# Audio_VU_LED.net
KiCad netlist of a schematic drawn in Altium Designer
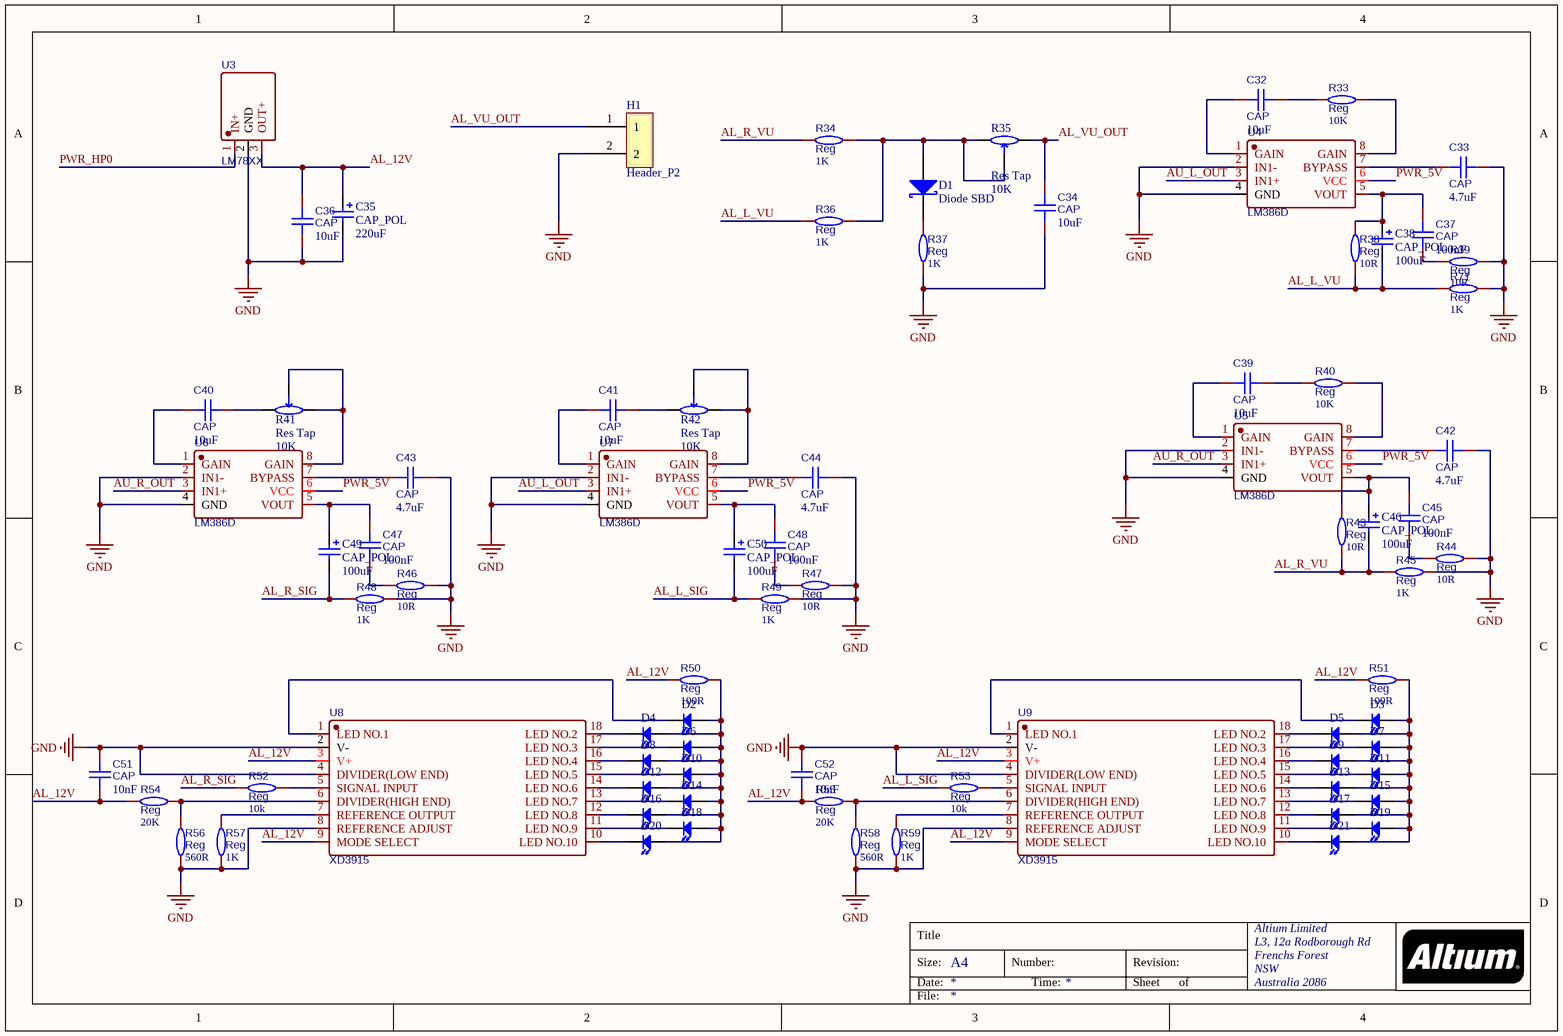
[diagram p0: Audio_VU_LED.SchDoc]

(export (version "E")
  (design (tool "Eeschema 10.0.6"))
  (components
    (comp (ref "C32")
      (value "CAP")
      (footprint "C0603")
      (description "Cap")
      (fields
        (field (name "BOM_SUPPLIER PART") "C302008")
        (field (name "BOM_MANUFACTURER PART") "0603B103K101CT")
        (field (name "ALTIUM_VALUE") "10uF")
        (field (name "CONTRIBUTOR") "LCSC")
      )
      (libsource (lib "Levent_lib") (part "CAP"))
    )
    (comp (ref "C33")
      (value "CAP")
      (footprint "C0603")
      (description "Cap")
      (fields
        (field (name "BOM_SUPPLIER PART") "C302008")
        (field (name "BOM_MANUFACTURER PART") "0603B103K101CT")
        (field (name "ALTIUM_VALUE") "4.7uF")
        (field (name "CONTRIBUTOR") "LCSC")
      )
      (libsource (lib "Levent_lib") (part "CAP"))
    )
    (comp (ref "C34")
      (value "CAP")
      (footprint "C0603")
      (description "Cap")
      (fields
        (field (name "BOM_SUPPLIER PART") "C302008")
        (field (name "BOM_MANUFACTURER PART") "0603B103K101CT")
        (field (name "ALTIUM_VALUE") "10uF")
        (field (name "CONTRIBUTOR") "LCSC")
      )
      (libsource (lib "Levent_lib") (part "CAP"))
    )
    (comp (ref "C35")
      (value "CAP_POL")
      (footprint "CAP_SMD_6.3mm")
      (description "极性电容")
      (fields (field (name "ALTIUM_VALUE") "220uF"))
      (libsource (lib "Levent_lib") (part "CAP_POL"))
    )
    (comp (ref "C36")
      (value "CAP")
      (footprint "C0603")
      (description "Cap")
      (fields
        (field (name "BOM_SUPPLIER PART") "C302008")
        (field (name "BOM_MANUFACTURER PART") "0603B103K101CT")
        (field (name "ALTIUM_VALUE") "10uF")
        (field (name "CONTRIBUTOR") "LCSC")
      )
      (libsource (lib "Levent_lib") (part "CAP"))
    )
    (comp (ref "C37")
      (value "CAP")
      (footprint "C0603")
      (description "Cap")
      (fields
        (field (name "BOM_SUPPLIER PART") "C302008")
        (field (name "BOM_MANUFACTURER PART") "0603B103K101CT")
        (field (name "ALTIUM_VALUE") "100nF")
        (field (name "CONTRIBUTOR") "LCSC")
      )
      (libsource (lib "Levent_lib") (part "CAP"))
    )
    (comp (ref "C38")
      (value "CAP_POL")
      (footprint "CAP_SMD_6.3mm")
      (description "极性电容")
      (fields (field (name "ALTIUM_VALUE") "100uF"))
      (libsource (lib "Levent_lib") (part "CAP_POL"))
    )
    (comp (ref "C39")
      (value "CAP")
      (footprint "C0603")
      (description "Cap")
      (fields
        (field (name "BOM_SUPPLIER PART") "C302008")
        (field (name "BOM_MANUFACTURER PART") "0603B103K101CT")
        (field (name "ALTIUM_VALUE") "10uF")
        (field (name "CONTRIBUTOR") "LCSC")
      )
      (libsource (lib "Levent_lib") (part "CAP"))
    )
    (comp (ref "C40")
      (value "CAP")
      (footprint "C0603")
      (description "Cap")
      (fields
        (field (name "BOM_SUPPLIER PART") "C302008")
        (field (name "BOM_MANUFACTURER PART") "0603B103K101CT")
        (field (name "ALTIUM_VALUE") "10uF")
        (field (name "CONTRIBUTOR") "LCSC")
      )
      (libsource (lib "Levent_lib") (part "CAP"))
    )
    (comp (ref "C41")
      (value "CAP")
      (footprint "C0603")
      (description "Cap")
      (fields
        (field (name "BOM_SUPPLIER PART") "C302008")
        (field (name "BOM_MANUFACTURER PART") "0603B103K101CT")
        (field (name "ALTIUM_VALUE") "10uF")
        (field (name "CONTRIBUTOR") "LCSC")
      )
      (libsource (lib "Levent_lib") (part "CAP"))
    )
    (comp (ref "C42")
      (value "CAP")
      (footprint "C0603")
      (description "Cap")
      (fields
        (field (name "BOM_SUPPLIER PART") "C302008")
        (field (name "BOM_MANUFACTURER PART") "0603B103K101CT")
        (field (name "ALTIUM_VALUE") "4.7uF")
        (field (name "CONTRIBUTOR") "LCSC")
      )
      (libsource (lib "Levent_lib") (part "CAP"))
    )
    (comp (ref "C43")
      (value "CAP")
      (footprint "C0603")
      (description "Cap")
      (fields
        (field (name "BOM_SUPPLIER PART") "C302008")
        (field (name "BOM_MANUFACTURER PART") "0603B103K101CT")
        (field (name "ALTIUM_VALUE") "4.7uF")
        (field (name "CONTRIBUTOR") "LCSC")
      )
      (libsource (lib "Levent_lib") (part "CAP"))
    )
    (comp (ref "C44")
      (value "CAP")
      (footprint "C0603")
      (description "Cap")
      (fields
        (field (name "BOM_SUPPLIER PART") "C302008")
        (field (name "BOM_MANUFACTURER PART") "0603B103K101CT")
        (field (name "ALTIUM_VALUE") "4.7uF")
        (field (name "CONTRIBUTOR") "LCSC")
      )
      (libsource (lib "Levent_lib") (part "CAP"))
    )
    (comp (ref "C45")
      (value "CAP")
      (footprint "C0603")
      (description "Cap")
      (fields
        (field (name "BOM_SUPPLIER PART") "C302008")
        (field (name "BOM_MANUFACTURER PART") "0603B103K101CT")
        (field (name "ALTIUM_VALUE") "100nF")
        (field (name "CONTRIBUTOR") "LCSC")
      )
      (libsource (lib "Levent_lib") (part "CAP"))
    )
    (comp (ref "C46")
      (value "CAP_POL")
      (footprint "CAP_SMD_6.3mm")
      (description "极性电容")
      (fields (field (name "ALTIUM_VALUE") "100uF"))
      (libsource (lib "Levent_lib") (part "CAP_POL"))
    )
    (comp (ref "C47")
      (value "CAP")
      (footprint "C0603")
      (description "Cap")
      (fields
        (field (name "BOM_SUPPLIER PART") "C302008")
        (field (name "BOM_MANUFACTURER PART") "0603B103K101CT")
        (field (name "ALTIUM_VALUE") "100nF")
        (field (name "CONTRIBUTOR") "LCSC")
      )
      (libsource (lib "Levent_lib") (part "CAP"))
    )
    (comp (ref "C48")
      (value "CAP")
      (footprint "C0603")
      (description "Cap")
      (fields
        (field (name "BOM_SUPPLIER PART") "C302008")
        (field (name "BOM_MANUFACTURER PART") "0603B103K101CT")
        (field (name "ALTIUM_VALUE") "100nF")
        (field (name "CONTRIBUTOR") "LCSC")
      )
      (libsource (lib "Levent_lib") (part "CAP"))
    )
    (comp (ref "C49")
      (value "CAP_POL")
      (footprint "CAP_SMD_6.3mm")
      (description "极性电容")
      (fields (field (name "ALTIUM_VALUE") "100uF"))
      (libsource (lib "Levent_lib") (part "CAP_POL"))
    )
    (comp (ref "C50")
      (value "CAP_POL")
      (footprint "CAP_SMD_6.3mm")
      (description "极性电容")
      (fields (field (name "ALTIUM_VALUE") "100uF"))
      (libsource (lib "Levent_lib") (part "CAP_POL"))
    )
    (comp (ref "C51")
      (value "CAP")
      (footprint "C0603")
      (description "Cap")
      (fields
        (field (name "BOM_SUPPLIER PART") "C302008")
        (field (name "BOM_MANUFACTURER PART") "0603B103K101CT")
        (field (name "ALTIUM_VALUE") "10nF")
        (field (name "CONTRIBUTOR") "LCSC")
      )
      (libsource (lib "Levent_lib") (part "CAP"))
    )
    (comp (ref "C52")
      (value "CAP")
      (footprint "C0603")
      (description "Cap")
      (fields
        (field (name "BOM_SUPPLIER PART") "C302008")
        (field (name "BOM_MANUFACTURER PART") "0603B103K101CT")
        (field (name "ALTIUM_VALUE") "10nF")
        (field (name "CONTRIBUTOR") "LCSC")
      )
      (libsource (lib "Levent_lib") (part "CAP"))
    )
    (comp (ref "D1")
      (value "Diode SBD")
      (footprint "SMA_L4.3")
      (description "Schottky Rectifier")
      (fields (field (name "PUBLISHER") "Altium Limited"))
      (libsource (lib "Levent_lib") (part "Diode SBD"))
    )
    (comp (ref "D2")
      (value "LED")
      (footprint "LED0603_Side")
      (fields (field (name "PUBLISHER") "Altium Limited"))
      (libsource (lib "Levent_lib") (part "LED0"))
    )
    (comp (ref "D3")
      (value "LED")
      (footprint "LED0603_Side")
      (fields (field (name "PUBLISHER") "Altium Limited"))
      (libsource (lib "Levent_lib") (part "LED0"))
    )
    (comp (ref "D4")
      (value "LED")
      (footprint "LED0603_Side")
      (fields (field (name "PUBLISHER") "Altium Limited"))
      (libsource (lib "Levent_lib") (part "LED0"))
    )
    (comp (ref "D5")
      (value "LED")
      (footprint "LED0603_Side")
      (fields (field (name "PUBLISHER") "Altium Limited"))
      (libsource (lib "Levent_lib") (part "LED0"))
    )
    (comp (ref "D6")
      (value "LED")
      (footprint "LED0603_Side")
      (fields (field (name "PUBLISHER") "Altium Limited"))
      (libsource (lib "Levent_lib") (part "LED0"))
    )
    (comp (ref "D7")
      (value "LED")
      (footprint "LED0603_Side")
      (fields (field (name "PUBLISHER") "Altium Limited"))
      (libsource (lib "Levent_lib") (part "LED0"))
    )
    (comp (ref "D8")
      (value "LED")
      (footprint "LED0603_Side")
      (fields (field (name "PUBLISHER") "Altium Limited"))
      (libsource (lib "Levent_lib") (part "LED0"))
    )
    (comp (ref "D9")
      (value "LED")
      (footprint "LED0603_Side")
      (fields (field (name "PUBLISHER") "Altium Limited"))
      (libsource (lib "Levent_lib") (part "LED0"))
    )
    (comp (ref "D10")
      (value "LED")
      (footprint "LED0603_Side")
      (fields (field (name "PUBLISHER") "Altium Limited"))
      (libsource (lib "Levent_lib") (part "LED0"))
    )
    (comp (ref "D11")
      (value "LED")
      (footprint "LED0603_Side")
      (fields (field (name "PUBLISHER") "Altium Limited"))
      (libsource (lib "Levent_lib") (part "LED0"))
    )
    (comp (ref "D12")
      (value "LED")
      (footprint "LED0603_Side")
      (fields (field (name "PUBLISHER") "Altium Limited"))
      (libsource (lib "Levent_lib") (part "LED0"))
    )
    (comp (ref "D13")
      (value "LED")
      (footprint "LED0603_Side")
      (fields (field (name "PUBLISHER") "Altium Limited"))
      (libsource (lib "Levent_lib") (part "LED0"))
    )
    (comp (ref "D14")
      (value "LED")
      (footprint "LED0603_Side")
      (fields (field (name "PUBLISHER") "Altium Limited"))
      (libsource (lib "Levent_lib") (part "LED0"))
    )
    (comp (ref "D15")
      (value "LED")
      (footprint "LED0603_Side")
      (fields (field (name "PUBLISHER") "Altium Limited"))
      (libsource (lib "Levent_lib") (part "LED0"))
    )
    (comp (ref "D16")
      (value "LED")
      (footprint "LED0603_Side")
      (fields (field (name "PUBLISHER") "Altium Limited"))
      (libsource (lib "Levent_lib") (part "LED0"))
    )
    (comp (ref "D17")
      (value "LED")
      (footprint "LED0603_Side")
      (fields (field (name "PUBLISHER") "Altium Limited"))
      (libsource (lib "Levent_lib") (part "LED0"))
    )
    (comp (ref "D18")
      (value "LED")
      (footprint "LED0603_Side")
      (fields (field (name "PUBLISHER") "Altium Limited"))
      (libsource (lib "Levent_lib") (part "LED0"))
    )
    (comp (ref "D19")
      (value "LED")
      (footprint "LED0603_Side")
      (fields (field (name "PUBLISHER") "Altium Limited"))
      (libsource (lib "Levent_lib") (part "LED0"))
    )
    (comp (ref "D20")
      (value "LED")
      (footprint "LED0603_Side")
      (fields (field (name "PUBLISHER") "Altium Limited"))
      (libsource (lib "Levent_lib") (part "LED0"))
    )
    (comp (ref "D21")
      (value "LED")
      (footprint "LED0603_Side")
      (fields (field (name "PUBLISHER") "Altium Limited"))
      (libsource (lib "Levent_lib") (part "LED0"))
    )
    (comp (ref "H1")
      (value "Header_P2")
      (footprint "H_2.54_P2")
      (description "2Pin排针")
      (libsource (lib "Levent_lib") (part "Header_P2"))
    )
    (comp (ref "R33")
      (value "Reg")
      (footprint "R0603")
      (description "电阻")
      (fields
        (field (name "BOM_SUPPLIER PART") "C465721")
        (field (name "BOM_MANUFACTURER PART") "AR03BTCX1002A")
        (field (name "ALTIUM_VALUE") "10K")
        (field (name "CONTRIBUTOR") "LCSC")
      )
      (libsource (lib "Levent_lib") (part "Res"))
    )
    (comp (ref "R34")
      (value "Reg")
      (footprint "R0603")
      (description "电阻")
      (fields
        (field (name "BOM_SUPPLIER PART") "C465721")
        (field (name "BOM_MANUFACTURER PART") "AR03BTCX1002A")
        (field (name "ALTIUM_VALUE") "1K")
        (field (name "CONTRIBUTOR") "LCSC")
      )
      (libsource (lib "Levent_lib") (part "Res"))
    )
    (comp (ref "R35")
      (value "Res Tap")
      (footprint "RES_TAP_HOR")
      (description "可调电阻")
      (fields (field (name "ALTIUM_VALUE") "10K") (field (name "PUBLISHER") "Altium Limited"))
      (libsource (lib "Levent_lib") (part "Res Tap"))
    )
    (comp (ref "R36")
      (value "Reg")
      (footprint "R0603")
      (description "电阻")
      (fields
        (field (name "BOM_SUPPLIER PART") "C465721")
        (field (name "BOM_MANUFACTURER PART") "AR03BTCX1002A")
        (field (name "ALTIUM_VALUE") "1K")
        (field (name "CONTRIBUTOR") "LCSC")
      )
      (libsource (lib "Levent_lib") (part "Res"))
    )
    (comp (ref "R37")
      (value "Reg")
      (footprint "R0603")
      (description "电阻")
      (fields
        (field (name "BOM_SUPPLIER PART") "C465721")
        (field (name "BOM_MANUFACTURER PART") "AR03BTCX1002A")
        (field (name "ALTIUM_VALUE") "1K")
        (field (name "CONTRIBUTOR") "LCSC")
      )
      (libsource (lib "Levent_lib") (part "Res"))
    )
    (comp (ref "R38")
      (value "Reg")
      (footprint "R0603")
      (description "电阻")
      (fields
        (field (name "BOM_SUPPLIER PART") "C465721")
        (field (name "BOM_MANUFACTURER PART") "AR03BTCX1002A")
        (field (name "ALTIUM_VALUE") "10R")
        (field (name "CONTRIBUTOR") "LCSC")
      )
      (libsource (lib "Levent_lib") (part "Res"))
    )
    (comp (ref "R39")
      (value "Reg")
      (footprint "R0603")
      (description "电阻")
      (fields
        (field (name "BOM_SUPPLIER PART") "C465721")
        (field (name "BOM_MANUFACTURER PART") "AR03BTCX1002A")
        (field (name "ALTIUM_VALUE") "10R")
        (field (name "CONTRIBUTOR") "LCSC")
      )
      (libsource (lib "Levent_lib") (part "Res"))
    )
    (comp (ref "R40")
      (value "Reg")
      (footprint "R0603")
      (description "电阻")
      (fields
        (field (name "BOM_SUPPLIER PART") "C465721")
        (field (name "BOM_MANUFACTURER PART") "AR03BTCX1002A")
        (field (name "ALTIUM_VALUE") "10K")
        (field (name "CONTRIBUTOR") "LCSC")
      )
      (libsource (lib "Levent_lib") (part "Res"))
    )
    (comp (ref "R41")
      (value "Res Tap")
      (footprint "RES_TAP_HOR")
      (description "可调电阻")
      (fields (field (name "ALTIUM_VALUE") "10K") (field (name "PUBLISHER") "Altium Limited"))
      (libsource (lib "Levent_lib") (part "Res Tap"))
    )
    (comp (ref "R42")
      (value "Res Tap")
      (footprint "RES_TAP_HOR")
      (description "可调电阻")
      (fields (field (name "ALTIUM_VALUE") "10K") (field (name "PUBLISHER") "Altium Limited"))
      (libsource (lib "Levent_lib") (part "Res Tap"))
    )
    (comp (ref "R43")
      (value "Reg")
      (footprint "R0603")
      (description "电阻")
      (fields
        (field (name "BOM_SUPPLIER PART") "C465721")
        (field (name "BOM_MANUFACTURER PART") "AR03BTCX1002A")
        (field (name "ALTIUM_VALUE") "10R")
        (field (name "CONTRIBUTOR") "LCSC")
      )
      (libsource (lib "Levent_lib") (part "Res"))
    )
    (comp (ref "R44")
      (value "Reg")
      (footprint "R0603")
      (description "电阻")
      (fields
        (field (name "BOM_SUPPLIER PART") "C465721")
        (field (name "BOM_MANUFACTURER PART") "AR03BTCX1002A")
        (field (name "ALTIUM_VALUE") "10R")
        (field (name "CONTRIBUTOR") "LCSC")
      )
      (libsource (lib "Levent_lib") (part "Res"))
    )
    (comp (ref "R45")
      (value "Reg")
      (footprint "R0603")
      (description "电阻")
      (fields
        (field (name "BOM_SUPPLIER PART") "C465721")
        (field (name "BOM_MANUFACTURER PART") "AR03BTCX1002A")
        (field (name "ALTIUM_VALUE") "1K")
        (field (name "CONTRIBUTOR") "LCSC")
      )
      (libsource (lib "Levent_lib") (part "Res"))
    )
    (comp (ref "R46")
      (value "Reg")
      (footprint "R0603")
      (description "电阻")
      (fields
        (field (name "BOM_SUPPLIER PART") "C465721")
        (field (name "BOM_MANUFACTURER PART") "AR03BTCX1002A")
        (field (name "ALTIUM_VALUE") "10R")
        (field (name "CONTRIBUTOR") "LCSC")
      )
      (libsource (lib "Levent_lib") (part "Res"))
    )
    (comp (ref "R47")
      (value "Reg")
      (footprint "R0603")
      (description "电阻")
      (fields
        (field (name "BOM_SUPPLIER PART") "C465721")
        (field (name "BOM_MANUFACTURER PART") "AR03BTCX1002A")
        (field (name "ALTIUM_VALUE") "10R")
        (field (name "CONTRIBUTOR") "LCSC")
      )
      (libsource (lib "Levent_lib") (part "Res"))
    )
    (comp (ref "R48")
      (value "Reg")
      (footprint "R0603")
      (description "电阻")
      (fields
        (field (name "BOM_SUPPLIER PART") "C465721")
        (field (name "BOM_MANUFACTURER PART") "AR03BTCX1002A")
        (field (name "ALTIUM_VALUE") "1K")
        (field (name "CONTRIBUTOR") "LCSC")
      )
      (libsource (lib "Levent_lib") (part "Res"))
    )
    (comp (ref "R49")
      (value "Reg")
      (footprint "R0603")
      (description "电阻")
      (fields
        (field (name "BOM_SUPPLIER PART") "C465721")
        (field (name "BOM_MANUFACTURER PART") "AR03BTCX1002A")
        (field (name "ALTIUM_VALUE") "1K")
        (field (name "CONTRIBUTOR") "LCSC")
      )
      (libsource (lib "Levent_lib") (part "Res"))
    )
    (comp (ref "R50")
      (value "Reg")
      (footprint "R0603")
      (description "电阻")
      (fields
        (field (name "BOM_SUPPLIER PART") "C465721")
        (field (name "BOM_MANUFACTURER PART") "AR03BTCX1002A")
        (field (name "ALTIUM_VALUE") "100R")
        (field (name "CONTRIBUTOR") "LCSC")
      )
      (libsource (lib "Levent_lib") (part "Res"))
    )
    (comp (ref "R51")
      (value "Reg")
      (footprint "R0603")
      (description "电阻")
      (fields
        (field (name "BOM_SUPPLIER PART") "C465721")
        (field (name "BOM_MANUFACTURER PART") "AR03BTCX1002A")
        (field (name "ALTIUM_VALUE") "100R")
        (field (name "CONTRIBUTOR") "LCSC")
      )
      (libsource (lib "Levent_lib") (part "Res"))
    )
    (comp (ref "R52")
      (value "Reg")
      (footprint "R0603")
      (description "电阻")
      (fields
        (field (name "BOM_SUPPLIER PART") "C465721")
        (field (name "BOM_MANUFACTURER PART") "AR03BTCX1002A")
        (field (name "ALTIUM_VALUE") "10k")
        (field (name "CONTRIBUTOR") "LCSC")
      )
      (libsource (lib "Levent_lib") (part "Res"))
    )
    (comp (ref "R53")
      (value "Reg")
      (footprint "R0603")
      (description "电阻")
      (fields
        (field (name "BOM_SUPPLIER PART") "C465721")
        (field (name "BOM_MANUFACTURER PART") "AR03BTCX1002A")
        (field (name "ALTIUM_VALUE") "10k")
        (field (name "CONTRIBUTOR") "LCSC")
      )
      (libsource (lib "Levent_lib") (part "Res"))
    )
    (comp (ref "R54")
      (value "Reg")
      (footprint "R0603")
      (description "电阻")
      (fields
        (field (name "BOM_SUPPLIER PART") "C465721")
        (field (name "BOM_MANUFACTURER PART") "AR03BTCX1002A")
        (field (name "ALTIUM_VALUE") "20K")
        (field (name "CONTRIBUTOR") "LCSC")
      )
      (libsource (lib "Levent_lib") (part "Res"))
    )
    (comp (ref "R55")
      (value "Reg")
      (footprint "R0603")
      (description "电阻")
      (fields
        (field (name "BOM_SUPPLIER PART") "C465721")
        (field (name "BOM_MANUFACTURER PART") "AR03BTCX1002A")
        (field (name "ALTIUM_VALUE") "20K")
        (field (name "CONTRIBUTOR") "LCSC")
      )
      (libsource (lib "Levent_lib") (part "Res"))
    )
    (comp (ref "R56")
      (value "Reg")
      (footprint "R0603")
      (description "电阻")
      (fields
        (field (name "BOM_SUPPLIER PART") "C465721")
        (field (name "BOM_MANUFACTURER PART") "AR03BTCX1002A")
        (field (name "ALTIUM_VALUE") "560R")
        (field (name "CONTRIBUTOR") "LCSC")
      )
      (libsource (lib "Levent_lib") (part "Res"))
    )
    (comp (ref "R57")
      (value "Reg")
      (footprint "R0603")
      (description "电阻")
      (fields
        (field (name "BOM_SUPPLIER PART") "C465721")
        (field (name "BOM_MANUFACTURER PART") "AR03BTCX1002A")
        (field (name "ALTIUM_VALUE") "1K")
        (field (name "CONTRIBUTOR") "LCSC")
      )
      (libsource (lib "Levent_lib") (part "Res"))
    )
    (comp (ref "R58")
      (value "Reg")
      (footprint "R0603")
      (description "电阻")
      (fields
        (field (name "BOM_SUPPLIER PART") "C465721")
        (field (name "BOM_MANUFACTURER PART") "AR03BTCX1002A")
        (field (name "ALTIUM_VALUE") "560R")
        (field (name "CONTRIBUTOR") "LCSC")
      )
      (libsource (lib "Levent_lib") (part "Res"))
    )
    (comp (ref "R59")
      (value "Reg")
      (footprint "R0603")
      (description "电阻")
      (fields
        (field (name "BOM_SUPPLIER PART") "C465721")
        (field (name "BOM_MANUFACTURER PART") "AR03BTCX1002A")
        (field (name "ALTIUM_VALUE") "1K")
        (field (name "CONTRIBUTOR") "LCSC")
      )
      (libsource (lib "Levent_lib") (part "Res"))
    )
    (comp (ref "R71")
      (value "Reg")
      (footprint "R0603")
      (description "电阻")
      (fields
        (field (name "BOM_SUPPLIER PART") "C465721")
        (field (name "BOM_MANUFACTURER PART") "AR03BTCX1002A")
        (field (name "ALTIUM_VALUE") "1K")
        (field (name "CONTRIBUTOR") "LCSC")
      )
      (libsource (lib "Levent_lib") (part "Res"))
    )
    (comp (ref "U3")
      (value "LM78XX")
      (footprint "TO-220-3_2.54")
      (description "三端稳压(正电压)")
      (fields
        (field (name "BOM_SUPPLIER PART") "C2902509")
        (field (name "BOM_MANUFACTURER PART") "LM7812T")
        (field (name "CONTRIBUTOR") "LCSC")
      )
      (libsource (lib "Levent_lib") (part "LM78XX"))
    )
    (comp (ref "U4")
      (value "LM386D")
      (footprint "SOP-8")
      (description "LM386")
      (fields (field (name "BOM_SUPPLIER PART") "C510560") (field (name "CONTRIBUTOR") "LCSC"))
      (libsource (lib "Levent_lib") (part "LM386D"))
    )
    (comp (ref "U5")
      (value "LM386D")
      (footprint "SOP-8")
      (description "LM386")
      (fields (field (name "BOM_SUPPLIER PART") "C510560") (field (name "CONTRIBUTOR") "LCSC"))
      (libsource (lib "Levent_lib") (part "LM386D"))
    )
    (comp (ref "U6")
      (value "LM386D")
      (footprint "SOP-8")
      (description "LM386")
      (fields (field (name "BOM_SUPPLIER PART") "C510560") (field (name "CONTRIBUTOR") "LCSC"))
      (libsource (lib "Levent_lib") (part "LM386D"))
    )
    (comp (ref "U7")
      (value "LM386D")
      (footprint "SOP-8")
      (description "LM386")
      (fields (field (name "BOM_SUPPLIER PART") "C510560") (field (name "CONTRIBUTOR") "LCSC"))
      (libsource (lib "Levent_lib") (part "LM386D"))
    )
    (comp (ref "U8")
      (value "XD3915")
      (footprint "DIP-18")
      (description "电平指示")
      (fields (field (name "BOM_SUPPLIER PART") "C609778") (field (name "CONTRIBUTOR") "LCSC"))
      (libsource (lib "Levent_lib") (part "LM3915"))
    )
    (comp (ref "U9")
      (value "XD3915")
      (footprint "DIP-18")
      (description "电平指示")
      (fields (field (name "BOM_SUPPLIER PART") "C609778") (field (name "CONTRIBUTOR") "LCSC"))
      (libsource (lib "Levent_lib") (part "LM3915"))
    )
  )
  (nets
    (net (code "1") (name "/AL_12V") (class "Default")
      (node (ref "C35") (pin "1") (pinfunction "1_1") (pintype "passive"))
      (node (ref "C36") (pin "1") (pinfunction "1_1") (pintype "passive"))
      (node (ref "C51") (pin "1") (pinfunction "1_1") (pintype "passive"))
      (node (ref "C52") (pin "1") (pinfunction "1_1") (pintype "passive"))
      (node (ref "R50") (pin "1") (pinfunction "1_1") (pintype "passive"))
      (node (ref "R51") (pin "1") (pinfunction "1_1") (pintype "passive"))
      (node (ref "R54") (pin "2") (pinfunction "2_2") (pintype "passive"))
      (node (ref "R55") (pin "2") (pinfunction "2_2") (pintype "passive"))
      (node (ref "U3") (pin "3") (pinfunction "OUT+_3") (pintype "passive"))
      (node (ref "U8") (pin "3") (pinfunction "V+_3") (pintype "passive"))
      (node (ref "U8") (pin "9") (pinfunction "MODE_SELECT_9") (pintype "passive"))
      (node (ref "U9") (pin "3") (pinfunction "V+_3") (pintype "passive"))
      (node (ref "U9") (pin "9") (pinfunction "MODE_SELECT_9") (pintype "passive"))
    )
    (net (code "2") (name "/AL_L_SIG") (class "Default")
      (node (ref "C50") (pin "2") (pinfunction "2_2") (pintype "passive"))
      (node (ref "R49") (pin "2") (pinfunction "2_2") (pintype "passive"))
      (node (ref "R53") (pin "2") (pinfunction "2_2") (pintype "passive"))
    )
    (net (code "3") (name "/AL_L_VU") (class "Default")
      (node (ref "C38") (pin "2") (pinfunction "2_2") (pintype "passive"))
      (node (ref "R36") (pin "2") (pinfunction "2_2") (pintype "passive"))
      (node (ref "R38") (pin "2") (pinfunction "2_2") (pintype "passive"))
      (node (ref "R71") (pin "2") (pinfunction "2_2") (pintype "passive"))
    )
    (net (code "4") (name "/AL_R_SIG") (class "Default")
      (node (ref "C49") (pin "2") (pinfunction "2_2") (pintype "passive"))
      (node (ref "R48") (pin "2") (pinfunction "2_2") (pintype "passive"))
      (node (ref "R52") (pin "2") (pinfunction "2_2") (pintype "passive"))
    )
    (net (code "5") (name "/AL_R_VU") (class "Default")
      (node (ref "C46") (pin "2") (pinfunction "2_2") (pintype "passive"))
      (node (ref "R34") (pin "2") (pinfunction "2_2") (pintype "passive"))
      (node (ref "R43") (pin "2") (pinfunction "2_2") (pintype "passive"))
      (node (ref "R45") (pin "2") (pinfunction "2_2") (pintype "passive"))
    )
    (net (code "6") (name "/AL_VU_OUT") (class "Default")
      (node (ref "C34") (pin "1") (pinfunction "1_1") (pintype "passive"))
      (node (ref "H1") (pin "1") (pinfunction "1_1") (pintype "passive"))
      (node (ref "R35") (pin "1") (pinfunction "A_1") (pintype "passive"))
    )
    (net (code "7") (name "/AU_L_OUT") (class "Default")
      (node (ref "U4") (pin "3") (pinfunction "IN1+_3") (pintype "passive"))
      (node (ref "U7") (pin "3") (pinfunction "IN1+_3") (pintype "passive"))
    )
    (net (code "8") (name "/AU_R_OUT") (class "Default")
      (node (ref "U5") (pin "3") (pinfunction "IN1+_3") (pintype "passive"))
      (node (ref "U6") (pin "3") (pinfunction "IN1+_3") (pintype "passive"))
    )
    (net (code "9") (name "/PWR_5V") (class "Default")
      (node (ref "U4") (pin "6") (pinfunction "VCC_6") (pintype "passive"))
      (node (ref "U5") (pin "6") (pinfunction "VCC_6") (pintype "passive"))
      (node (ref "U6") (pin "6") (pinfunction "VCC_6") (pintype "passive"))
      (node (ref "U7") (pin "6") (pinfunction "VCC_6") (pintype "passive"))
    )
    (net (code "10") (name "/PWR_HP0") (class "Default")
      (node (ref "U3") (pin "1") (pinfunction "IN+_1") (pintype "passive"))
    )
    (net (code "11") (name "GND") (class "Default")
      (node (ref "C33") (pin "2") (pinfunction "2_2") (pintype "passive"))
      (node (ref "C34") (pin "2") (pinfunction "2_2") (pintype "passive"))
      (node (ref "C35") (pin "2") (pinfunction "2_2") (pintype "passive"))
      (node (ref "C36") (pin "2") (pinfunction "2_2") (pintype "passive"))
      (node (ref "C42") (pin "2") (pinfunction "2_2") (pintype "passive"))
      (node (ref "C43") (pin "2") (pinfunction "2_2") (pintype "passive"))
      (node (ref "C44") (pin "2") (pinfunction "2_2") (pintype "passive"))
      (node (ref "C51") (pin "2") (pinfunction "2_2") (pintype "passive"))
      (node (ref "C52") (pin "2") (pinfunction "2_2") (pintype "passive"))
      (node (ref "H1") (pin "2") (pinfunction "2_2") (pintype "passive"))
      (node (ref "R37") (pin "2") (pinfunction "2_2") (pintype "passive"))
      (node (ref "R39") (pin "1") (pinfunction "1_1") (pintype "passive"))
      (node (ref "R44") (pin "1") (pinfunction "1_1") (pintype "passive"))
      (node (ref "R45") (pin "1") (pinfunction "1_1") (pintype "passive"))
      (node (ref "R46") (pin "1") (pinfunction "1_1") (pintype "passive"))
      (node (ref "R47") (pin "1") (pinfunction "1_1") (pintype "passive"))
      (node (ref "R48") (pin "1") (pinfunction "1_1") (pintype "passive"))
      (node (ref "R49") (pin "1") (pinfunction "1_1") (pintype "passive"))
      (node (ref "R56") (pin "2") (pinfunction "2_2") (pintype "passive"))
      (node (ref "R57") (pin "2") (pinfunction "2_2") (pintype "passive"))
      (node (ref "R58") (pin "2") (pinfunction "2_2") (pintype "passive"))
      (node (ref "R59") (pin "2") (pinfunction "2_2") (pintype "passive"))
      (node (ref "R71") (pin "1") (pinfunction "1_1") (pintype "passive"))
      (node (ref "U3") (pin "2") (pinfunction "GND_2") (pintype "passive"))
      (node (ref "U4") (pin "2") (pinfunction "IN1-_2") (pintype "passive"))
      (node (ref "U4") (pin "4") (pinfunction "GND_4") (pintype "passive"))
      (node (ref "U5") (pin "2") (pinfunction "IN1-_2") (pintype "passive"))
      (node (ref "U5") (pin "4") (pinfunction "GND_4") (pintype "passive"))
      (node (ref "U6") (pin "2") (pinfunction "IN1-_2") (pintype "passive"))
      (node (ref "U6") (pin "4") (pinfunction "GND_4") (pintype "passive"))
      (node (ref "U7") (pin "2") (pinfunction "IN1-_2") (pintype "passive"))
      (node (ref "U7") (pin "4") (pinfunction "GND_4") (pintype "passive"))
      (node (ref "U8") (pin "2") (pinfunction "V-_2") (pintype "passive"))
      (node (ref "U8") (pin "4") (pinfunction "DIVIDER(LOW_END)_4") (pintype "passive"))
      (node (ref "U8") (pin "8") (pinfunction "REFERENCE_ADJUST_8") (pintype "passive"))
      (node (ref "U9") (pin "2") (pinfunction "V-_2") (pintype "passive"))
      (node (ref "U9") (pin "4") (pinfunction "DIVIDER(LOW_END)_4") (pintype "passive"))
      (node (ref "U9") (pin "8") (pinfunction "REFERENCE_ADJUST_8") (pintype "passive"))
    )
    (net (code "12") (name "Net-(C32-Pad1)") (class "Default")
      (node (ref "C32") (pin "1") (pinfunction "1_1") (pintype "passive"))
      (node (ref "U4") (pin "1") (pinfunction "GAIN_1") (pintype "passive"))
    )
    (net (code "13") (name "Net-(C32-Pad2)") (class "Default")
      (node (ref "C32") (pin "2") (pinfunction "2_2") (pintype "passive"))
      (node (ref "R33") (pin "2") (pinfunction "2_2") (pintype "passive"))
    )
    (net (code "14") (name "Net-(C37-Pad1)") (class "Default")
      (node (ref "C37") (pin "1") (pinfunction "1_1") (pintype "passive"))
      (node (ref "R39") (pin "2") (pinfunction "2_2") (pintype "passive"))
    )
    (net (code "15") (name "Net-(C39-Pad1)") (class "Default")
      (node (ref "C39") (pin "1") (pinfunction "1_1") (pintype "passive"))
      (node (ref "U5") (pin "1") (pinfunction "GAIN_1") (pintype "passive"))
    )
    (net (code "16") (name "Net-(C39-Pad2)") (class "Default")
      (node (ref "C39") (pin "2") (pinfunction "2_2") (pintype "passive"))
      (node (ref "R40") (pin "2") (pinfunction "2_2") (pintype "passive"))
    )
    (net (code "17") (name "Net-(C40-Pad1)") (class "Default")
      (node (ref "C40") (pin "1") (pinfunction "1_1") (pintype "passive"))
      (node (ref "U6") (pin "1") (pinfunction "GAIN_1") (pintype "passive"))
    )
    (net (code "18") (name "Net-(C41-Pad1)") (class "Default")
      (node (ref "C41") (pin "1") (pinfunction "1_1") (pintype "passive"))
      (node (ref "U7") (pin "1") (pinfunction "GAIN_1") (pintype "passive"))
    )
    (net (code "19") (name "Net-(C45-Pad1)") (class "Default")
      (node (ref "C45") (pin "1") (pinfunction "1_1") (pintype "passive"))
      (node (ref "R44") (pin "2") (pinfunction "2_2") (pintype "passive"))
    )
    (net (code "20") (name "Net-(C47-Pad1)") (class "Default")
      (node (ref "C47") (pin "1") (pinfunction "1_1") (pintype "passive"))
      (node (ref "R46") (pin "2") (pinfunction "2_2") (pintype "passive"))
    )
    (net (code "21") (name "Net-(C48-Pad1)") (class "Default")
      (node (ref "C48") (pin "1") (pinfunction "1_1") (pintype "passive"))
      (node (ref "R47") (pin "2") (pinfunction "2_2") (pintype "passive"))
    )
    (net (code "22") (name "Net-(D1-A)") (class "Default")
      (node (ref "D1") (pin "2") (pinfunction "A_2") (pintype "passive"))
      (node (ref "R34") (pin "1") (pinfunction "1_1") (pintype "passive"))
      (node (ref "R35") (pin "2") (pinfunction "B_2") (pintype "passive"))
      (node (ref "R35") (pin "3") (pinfunction "TAP_3") (pintype "passive"))
      (node (ref "R36") (pin "1") (pinfunction "1_1") (pintype "passive"))
    )
    (net (code "23") (name "Net-(D1-K)") (class "Default")
      (node (ref "D1") (pin "1") (pinfunction "K_1") (pintype "passive"))
      (node (ref "R37") (pin "1") (pinfunction "1_1") (pintype "passive"))
    )
    (net (code "24") (name "Net-(D2-K)") (class "Default")
      (node (ref "D2") (pin "1") (pinfunction "K_1") (pintype "passive"))
      (node (ref "U8") (pin "1") (pinfunction "LED_NO.1_1") (pintype "passive"))
    )
    (net (code "25") (name "Net-(D3-K)") (class "Default")
      (node (ref "D3") (pin "1") (pinfunction "K_1") (pintype "passive"))
      (node (ref "U9") (pin "1") (pinfunction "LED_NO.1_1") (pintype "passive"))
    )
    (net (code "26") (name "Net-(D4-K)") (class "Default")
      (node (ref "D4") (pin "1") (pinfunction "K_1") (pintype "passive"))
      (node (ref "U8") (pin "18") (pinfunction "LED_NO.2_18") (pintype "passive"))
    )
    (net (code "27") (name "Net-(D5-K)") (class "Default")
      (node (ref "D5") (pin "1") (pinfunction "K_1") (pintype "passive"))
      (node (ref "U9") (pin "18") (pinfunction "LED_NO.2_18") (pintype "passive"))
    )
    (net (code "28") (name "Net-(D6-K)") (class "Default")
      (node (ref "D6") (pin "1") (pinfunction "K_1") (pintype "passive"))
      (node (ref "U8") (pin "17") (pinfunction "LED_NO.3_17") (pintype "passive"))
    )
    (net (code "29") (name "Net-(D7-K)") (class "Default")
      (node (ref "D7") (pin "1") (pinfunction "K_1") (pintype "passive"))
      (node (ref "U9") (pin "17") (pinfunction "LED_NO.3_17") (pintype "passive"))
    )
    (net (code "30") (name "Net-(D8-K)") (class "Default")
      (node (ref "D8") (pin "1") (pinfunction "K_1") (pintype "passive"))
      (node (ref "U8") (pin "16") (pinfunction "LED_NO.4_16") (pintype "passive"))
    )
    (net (code "31") (name "Net-(D9-K)") (class "Default")
      (node (ref "D9") (pin "1") (pinfunction "K_1") (pintype "passive"))
      (node (ref "U9") (pin "16") (pinfunction "LED_NO.4_16") (pintype "passive"))
    )
    (net (code "32") (name "Net-(D10-A)") (class "Default")
      (node (ref "D10") (pin "2") (pinfunction "A_2") (pintype "passive"))
      (node (ref "D12") (pin "2") (pinfunction "A_2") (pintype "passive"))
      (node (ref "D14") (pin "2") (pinfunction "A_2") (pintype "passive"))
      (node (ref "D16") (pin "2") (pinfunction "A_2") (pintype "passive"))
      (node (ref "D18") (pin "2") (pinfunction "A_2") (pintype "passive"))
      (node (ref "D2") (pin "2") (pinfunction "A_2") (pintype "passive"))
      (node (ref "D20") (pin "2") (pinfunction "A_2") (pintype "passive"))
      (node (ref "D4") (pin "2") (pinfunction "A_2") (pintype "passive"))
      (node (ref "D6") (pin "2") (pinfunction "A_2") (pintype "passive"))
      (node (ref "D8") (pin "2") (pinfunction "A_2") (pintype "passive"))
      (node (ref "R50") (pin "2") (pinfunction "2_2") (pintype "passive"))
    )
    (net (code "33") (name "Net-(D10-K)") (class "Default")
      (node (ref "D10") (pin "1") (pinfunction "K_1") (pintype "passive"))
      (node (ref "U8") (pin "15") (pinfunction "LED_NO.5_15") (pintype "passive"))
    )
    (net (code "34") (name "Net-(D11-A)") (class "Default")
      (node (ref "D11") (pin "2") (pinfunction "A_2") (pintype "passive"))
      (node (ref "D13") (pin "2") (pinfunction "A_2") (pintype "passive"))
      (node (ref "D15") (pin "2") (pinfunction "A_2") (pintype "passive"))
      (node (ref "D17") (pin "2") (pinfunction "A_2") (pintype "passive"))
      (node (ref "D19") (pin "2") (pinfunction "A_2") (pintype "passive"))
      (node (ref "D21") (pin "2") (pinfunction "A_2") (pintype "passive"))
      (node (ref "D3") (pin "2") (pinfunction "A_2") (pintype "passive"))
      (node (ref "D5") (pin "2") (pinfunction "A_2") (pintype "passive"))
      (node (ref "D7") (pin "2") (pinfunction "A_2") (pintype "passive"))
      (node (ref "D9") (pin "2") (pinfunction "A_2") (pintype "passive"))
      (node (ref "R51") (pin "2") (pinfunction "2_2") (pintype "passive"))
    )
    (net (code "35") (name "Net-(D11-K)") (class "Default")
      (node (ref "D11") (pin "1") (pinfunction "K_1") (pintype "passive"))
      (node (ref "U9") (pin "15") (pinfunction "LED_NO.5_15") (pintype "passive"))
    )
    (net (code "36") (name "Net-(D12-K)") (class "Default")
      (node (ref "D12") (pin "1") (pinfunction "K_1") (pintype "passive"))
      (node (ref "U8") (pin "14") (pinfunction "LED_NO.6_14") (pintype "passive"))
    )
    (net (code "37") (name "Net-(D13-K)") (class "Default")
      (node (ref "D13") (pin "1") (pinfunction "K_1") (pintype "passive"))
      (node (ref "U9") (pin "14") (pinfunction "LED_NO.6_14") (pintype "passive"))
    )
    (net (code "38") (name "Net-(D14-K)") (class "Default")
      (node (ref "D14") (pin "1") (pinfunction "K_1") (pintype "passive"))
      (node (ref "U8") (pin "13") (pinfunction "LED_NO.7_13") (pintype "passive"))
    )
    (net (code "39") (name "Net-(D15-K)") (class "Default")
      (node (ref "D15") (pin "1") (pinfunction "K_1") (pintype "passive"))
      (node (ref "U9") (pin "13") (pinfunction "LED_NO.7_13") (pintype "passive"))
    )
    (net (code "40") (name "Net-(D16-K)") (class "Default")
      (node (ref "D16") (pin "1") (pinfunction "K_1") (pintype "passive"))
      (node (ref "U8") (pin "12") (pinfunction "LED_NO.8_12") (pintype "passive"))
    )
    (net (code "41") (name "Net-(D17-K)") (class "Default")
      (node (ref "D17") (pin "1") (pinfunction "K_1") (pintype "passive"))
      (node (ref "U9") (pin "12") (pinfunction "LED_NO.8_12") (pintype "passive"))
    )
    (net (code "42") (name "Net-(D18-K)") (class "Default")
      (node (ref "D18") (pin "1") (pinfunction "K_1") (pintype "passive"))
      (node (ref "U8") (pin "11") (pinfunction "LED_NO.9_11") (pintype "passive"))
    )
    (net (code "43") (name "Net-(D19-K)") (class "Default")
      (node (ref "D19") (pin "1") (pinfunction "K_1") (pintype "passive"))
      (node (ref "U9") (pin "11") (pinfunction "LED_NO.9_11") (pintype "passive"))
    )
    (net (code "44") (name "Net-(D20-K)") (class "Default")
      (node (ref "D20") (pin "1") (pinfunction "K_1") (pintype "passive"))
      (node (ref "U8") (pin "10") (pinfunction "LED_NO.10_10") (pintype "passive"))
    )
    (net (code "45") (name "Net-(D21-K)") (class "Default")
      (node (ref "D21") (pin "1") (pinfunction "K_1") (pintype "passive"))
      (node (ref "U9") (pin "10") (pinfunction "LED_NO.10_10") (pintype "passive"))
    )
    (net (code "46") (name "Net-(R33-Pad1)") (class "Default")
      (node (ref "R33") (pin "1") (pinfunction "1_1") (pintype "passive"))
      (node (ref "U4") (pin "8") (pinfunction "GAIN_8") (pintype "passive"))
    )
    (net (code "47") (name "Net-(R40-Pad1)") (class "Default")
      (node (ref "R40") (pin "1") (pinfunction "1_1") (pintype "passive"))
      (node (ref "U5") (pin "8") (pinfunction "GAIN_8") (pintype "passive"))
    )
    (net (code "48") (name "Net-(R41-A)") (class "Default")
      (node (ref "C40") (pin "2") (pinfunction "2_2") (pintype "passive"))
      (node (ref "R41") (pin "1") (pinfunction "A_1") (pintype "passive"))
    )
    (net (code "49") (name "Net-(R41-B)") (class "Default")
      (node (ref "R41") (pin "2") (pinfunction "B_2") (pintype "passive"))
      (node (ref "R41") (pin "3") (pinfunction "TAP_3") (pintype "passive"))
      (node (ref "U6") (pin "8") (pinfunction "GAIN_8") (pintype "passive"))
    )
    (net (code "50") (name "Net-(R42-A)") (class "Default")
      (node (ref "C41") (pin "2") (pinfunction "2_2") (pintype "passive"))
      (node (ref "R42") (pin "1") (pinfunction "A_1") (pintype "passive"))
    )
    (net (code "51") (name "Net-(R42-B)") (class "Default")
      (node (ref "R42") (pin "2") (pinfunction "B_2") (pintype "passive"))
      (node (ref "R42") (pin "3") (pinfunction "TAP_3") (pintype "passive"))
      (node (ref "U7") (pin "8") (pinfunction "GAIN_8") (pintype "passive"))
    )
    (net (code "52") (name "Net-(U4-BYPASS)") (class "Default")
      (node (ref "C33") (pin "1") (pinfunction "1_1") (pintype "passive"))
      (node (ref "U4") (pin "7") (pinfunction "BYPASS_7") (pintype "passive"))
    )
    (net (code "53") (name "Net-(U4-VOUT)") (class "Default")
      (node (ref "C37") (pin "2") (pinfunction "2_2") (pintype "passive"))
      (node (ref "C38") (pin "1") (pinfunction "1_1") (pintype "passive"))
      (node (ref "R38") (pin "1") (pinfunction "1_1") (pintype "passive"))
      (node (ref "U4") (pin "5") (pinfunction "VOUT_5") (pintype "passive"))
    )
    (net (code "54") (name "Net-(U5-BYPASS)") (class "Default")
      (node (ref "C42") (pin "1") (pinfunction "1_1") (pintype "passive"))
      (node (ref "U5") (pin "7") (pinfunction "BYPASS_7") (pintype "passive"))
    )
    (net (code "55") (name "Net-(U5-VOUT)") (class "Default")
      (node (ref "C45") (pin "2") (pinfunction "2_2") (pintype "passive"))
      (node (ref "C46") (pin "1") (pinfunction "1_1") (pintype "passive"))
      (node (ref "R43") (pin "1") (pinfunction "1_1") (pintype "passive"))
      (node (ref "U5") (pin "5") (pinfunction "VOUT_5") (pintype "passive"))
    )
    (net (code "56") (name "Net-(U6-BYPASS)") (class "Default")
      (node (ref "C43") (pin "1") (pinfunction "1_1") (pintype "passive"))
      (node (ref "U6") (pin "7") (pinfunction "BYPASS_7") (pintype "passive"))
    )
    (net (code "57") (name "Net-(U6-VOUT)") (class "Default")
      (node (ref "C47") (pin "2") (pinfunction "2_2") (pintype "passive"))
      (node (ref "C49") (pin "1") (pinfunction "1_1") (pintype "passive"))
      (node (ref "U6") (pin "5") (pinfunction "VOUT_5") (pintype "passive"))
    )
    (net (code "58") (name "Net-(U7-BYPASS)") (class "Default")
      (node (ref "C44") (pin "1") (pinfunction "1_1") (pintype "passive"))
      (node (ref "U7") (pin "7") (pinfunction "BYPASS_7") (pintype "passive"))
    )
    (net (code "59") (name "Net-(U7-VOUT)") (class "Default")
      (node (ref "C48") (pin "2") (pinfunction "2_2") (pintype "passive"))
      (node (ref "C50") (pin "1") (pinfunction "1_1") (pintype "passive"))
      (node (ref "U7") (pin "5") (pinfunction "VOUT_5") (pintype "passive"))
    )
    (net (code "60") (name "Net-(U8-DIVIDER(HIGH_END))") (class "Default")
      (node (ref "R54") (pin "1") (pinfunction "1_1") (pintype "passive"))
      (node (ref "R56") (pin "1") (pinfunction "1_1") (pintype "passive"))
      (node (ref "U8") (pin "6") (pinfunction "DIVIDER(HIGH_END)_6") (pintype "passive"))
    )
    (net (code "61") (name "Net-(U8-REFERENCE_OUTPUT)") (class "Default")
      (node (ref "R57") (pin "1") (pinfunction "1_1") (pintype "passive"))
      (node (ref "U8") (pin "7") (pinfunction "REFERENCE_OUTPUT_7") (pintype "passive"))
    )
    (net (code "62") (name "Net-(U8-SIGNAL_INPUT)") (class "Default")
      (node (ref "R52") (pin "1") (pinfunction "1_1") (pintype "passive"))
      (node (ref "U8") (pin "5") (pinfunction "SIGNAL_INPUT_5") (pintype "passive"))
    )
    (net (code "63") (name "Net-(U9-DIVIDER(HIGH_END))") (class "Default")
      (node (ref "R55") (pin "1") (pinfunction "1_1") (pintype "passive"))
      (node (ref "R58") (pin "1") (pinfunction "1_1") (pintype "passive"))
      (node (ref "U9") (pin "6") (pinfunction "DIVIDER(HIGH_END)_6") (pintype "passive"))
    )
    (net (code "64") (name "Net-(U9-REFERENCE_OUTPUT)") (class "Default")
      (node (ref "R59") (pin "1") (pinfunction "1_1") (pintype "passive"))
      (node (ref "U9") (pin "7") (pinfunction "REFERENCE_OUTPUT_7") (pintype "passive"))
    )
    (net (code "65") (name "Net-(U9-SIGNAL_INPUT)") (class "Default")
      (node (ref "R53") (pin "1") (pinfunction "1_1") (pintype "passive"))
      (node (ref "U9") (pin "5") (pinfunction "SIGNAL_INPUT_5") (pintype "passive"))
    )
  )
)
